# untitled.net
KiCad netlist of a schematic drawn in EAGLE
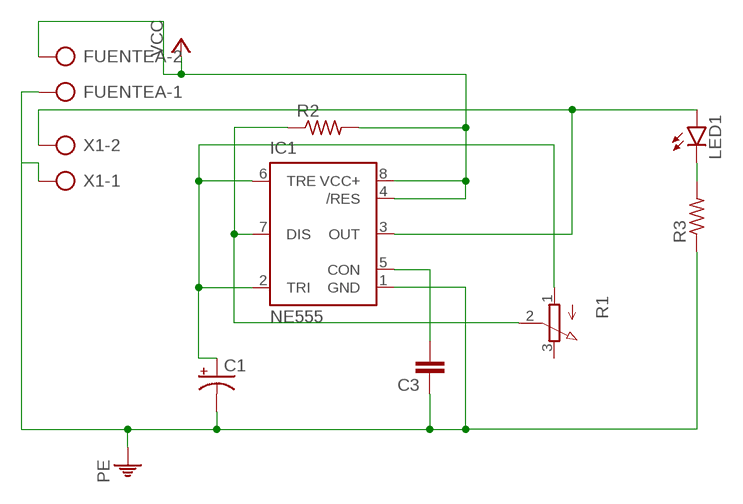
[diagram p0: schematic, sheet 1]

(export (version "E")
  (design (tool "Eeschema 10.0.6"))
  (components
    (comp (ref "C1")
      (value "CPOL-USE1.8-4")
      (footprint "eagle-import:E1,8-4")
      (libsource (lib "eagle-import") (part "CPOL-USE1.8-4"))
    )
    (comp (ref "C3")
      (value "C2,5-3")
      (footprint "eagle-import:C2.5-3")
      (libsource (lib "eagle-import") (part "C2,5-3"))
    )
    (comp (ref "FUENTEA")
      (value "AK500/2-H")
      (footprint "eagle-import:AK500_2-H")
      (libsource (lib "eagle-import") (part "AK500/2-H"))
    )
    (comp (ref "IC1")
      (value "NE555")
      (footprint "eagle-import:DIL-08")
      (fields (field (name "MF") "Arrow Electronics") (field (name "MPN") "NE555N"))
      (libsource (lib "eagle-import") (part "NE555"))
    )
    (comp (ref "LED1")
      (value "LED5MM")
      (footprint "eagle-import:LED5MM")
      (libsource (lib "eagle-import") (part "LED5MM"))
    )
    (comp (ref "R1")
      (value "3RP/1610N")
      (footprint "eagle-import:3RP_1610N")
      (libsource (lib "eagle-import") (part "3RP/1610N"))
    )
    (comp (ref "R2")
      (value "R-US_0204/7")
      (footprint "eagle-import:0204_7")
      (libsource (lib "eagle-import") (part "R-US_0204/7"))
    )
    (comp (ref "R3")
      (value "R-US_0204/7")
      (footprint "eagle-import:0204_7")
      (libsource (lib "eagle-import") (part "R-US_0204/7"))
    )
    (comp (ref "X1")
      (value "AK500/2-H")
      (footprint "eagle-import:AK500_2-H")
      (libsource (lib "eagle-import") (part "AK500/2-H"))
    )
  )
  (nets
    (net (code "1") (name "Net-(IC1-CON)") (class "Default")
      (node (ref "C3") (pin "2") (pinfunction "2_2") (pintype "passive"))
      (node (ref "IC1") (pin "5") (pinfunction "CON_5") (pintype "input"))
    )
    (net (code "2") (name "Net-(IC1-DIS)") (class "Default")
      (node (ref "IC1") (pin "7") (pinfunction "DIS_7") (pintype "input"))
      (node (ref "R1") (pin "2") (pinfunction "S_2") (pintype "passive"))
      (node (ref "R2") (pin "1") (pinfunction "1_1") (pintype "passive"))
    )
    (net (code "3") (name "Net-(IC1-OUT)") (class "Default")
      (node (ref "IC1") (pin "3") (pinfunction "OUT_3") (pintype "output"))
      (node (ref "LED1") (pin "A") (pinfunction "A_A") (pintype "passive"))
      (node (ref "X1") (pin "2") (pinfunction "KL_2") (pintype "passive"))
    )
    (net (code "4") (name "Net-(IC1-TRE)") (class "Default")
      (node (ref "C1") (pin "+") (pinfunction "+_+") (pintype "passive"))
      (node (ref "IC1") (pin "2") (pinfunction "TRI_2") (pintype "input"))
      (node (ref "IC1") (pin "6") (pinfunction "TRE_6") (pintype "input"))
      (node (ref "R1") (pin "1") (pinfunction "A_1") (pintype "passive"))
    )
    (net (code "5") (name "Net-(LED1-C)") (class "Default")
      (node (ref "LED1") (pin "K") (pinfunction "C_K") (pintype "passive"))
      (node (ref "R3") (pin "2") (pinfunction "2_2") (pintype "passive"))
    )
    (net (code "6") (name "PE") (class "Default")
      (node (ref "C1") (pin "-") (pinfunction "-_-") (pintype "passive"))
      (node (ref "C3") (pin "1") (pinfunction "1_1") (pintype "passive"))
      (node (ref "FUENTEA") (pin "1") (pinfunction "KL_1") (pintype "passive"))
      (node (ref "IC1") (pin "1") (pinfunction "GND_1") (pintype "power_in"))
      (node (ref "R3") (pin "1") (pinfunction "1_1") (pintype "passive"))
      (node (ref "X1") (pin "1") (pinfunction "KL_1") (pintype "passive"))
    )
    (net (code "7") (name "VCC") (class "Default")
      (node (ref "FUENTEA") (pin "2") (pinfunction "KL_2") (pintype "passive"))
      (node (ref "IC1") (pin "4") (pinfunction "/RES_4") (pintype "input"))
      (node (ref "IC1") (pin "8") (pinfunction "VCC+_8") (pintype "power_in"))
      (node (ref "R2") (pin "2") (pinfunction "2_2") (pintype "passive"))
    )
    (net (code "8") (name "unconnected-(R1-E-Pad3)") (class "Default")
      (node (ref "R1") (pin "3") (pinfunction "E_3") (pintype "passive"))
    )
  )
)
